# AdelinoR2.net
KiCad netlist of a schematic drawn in EAGLE
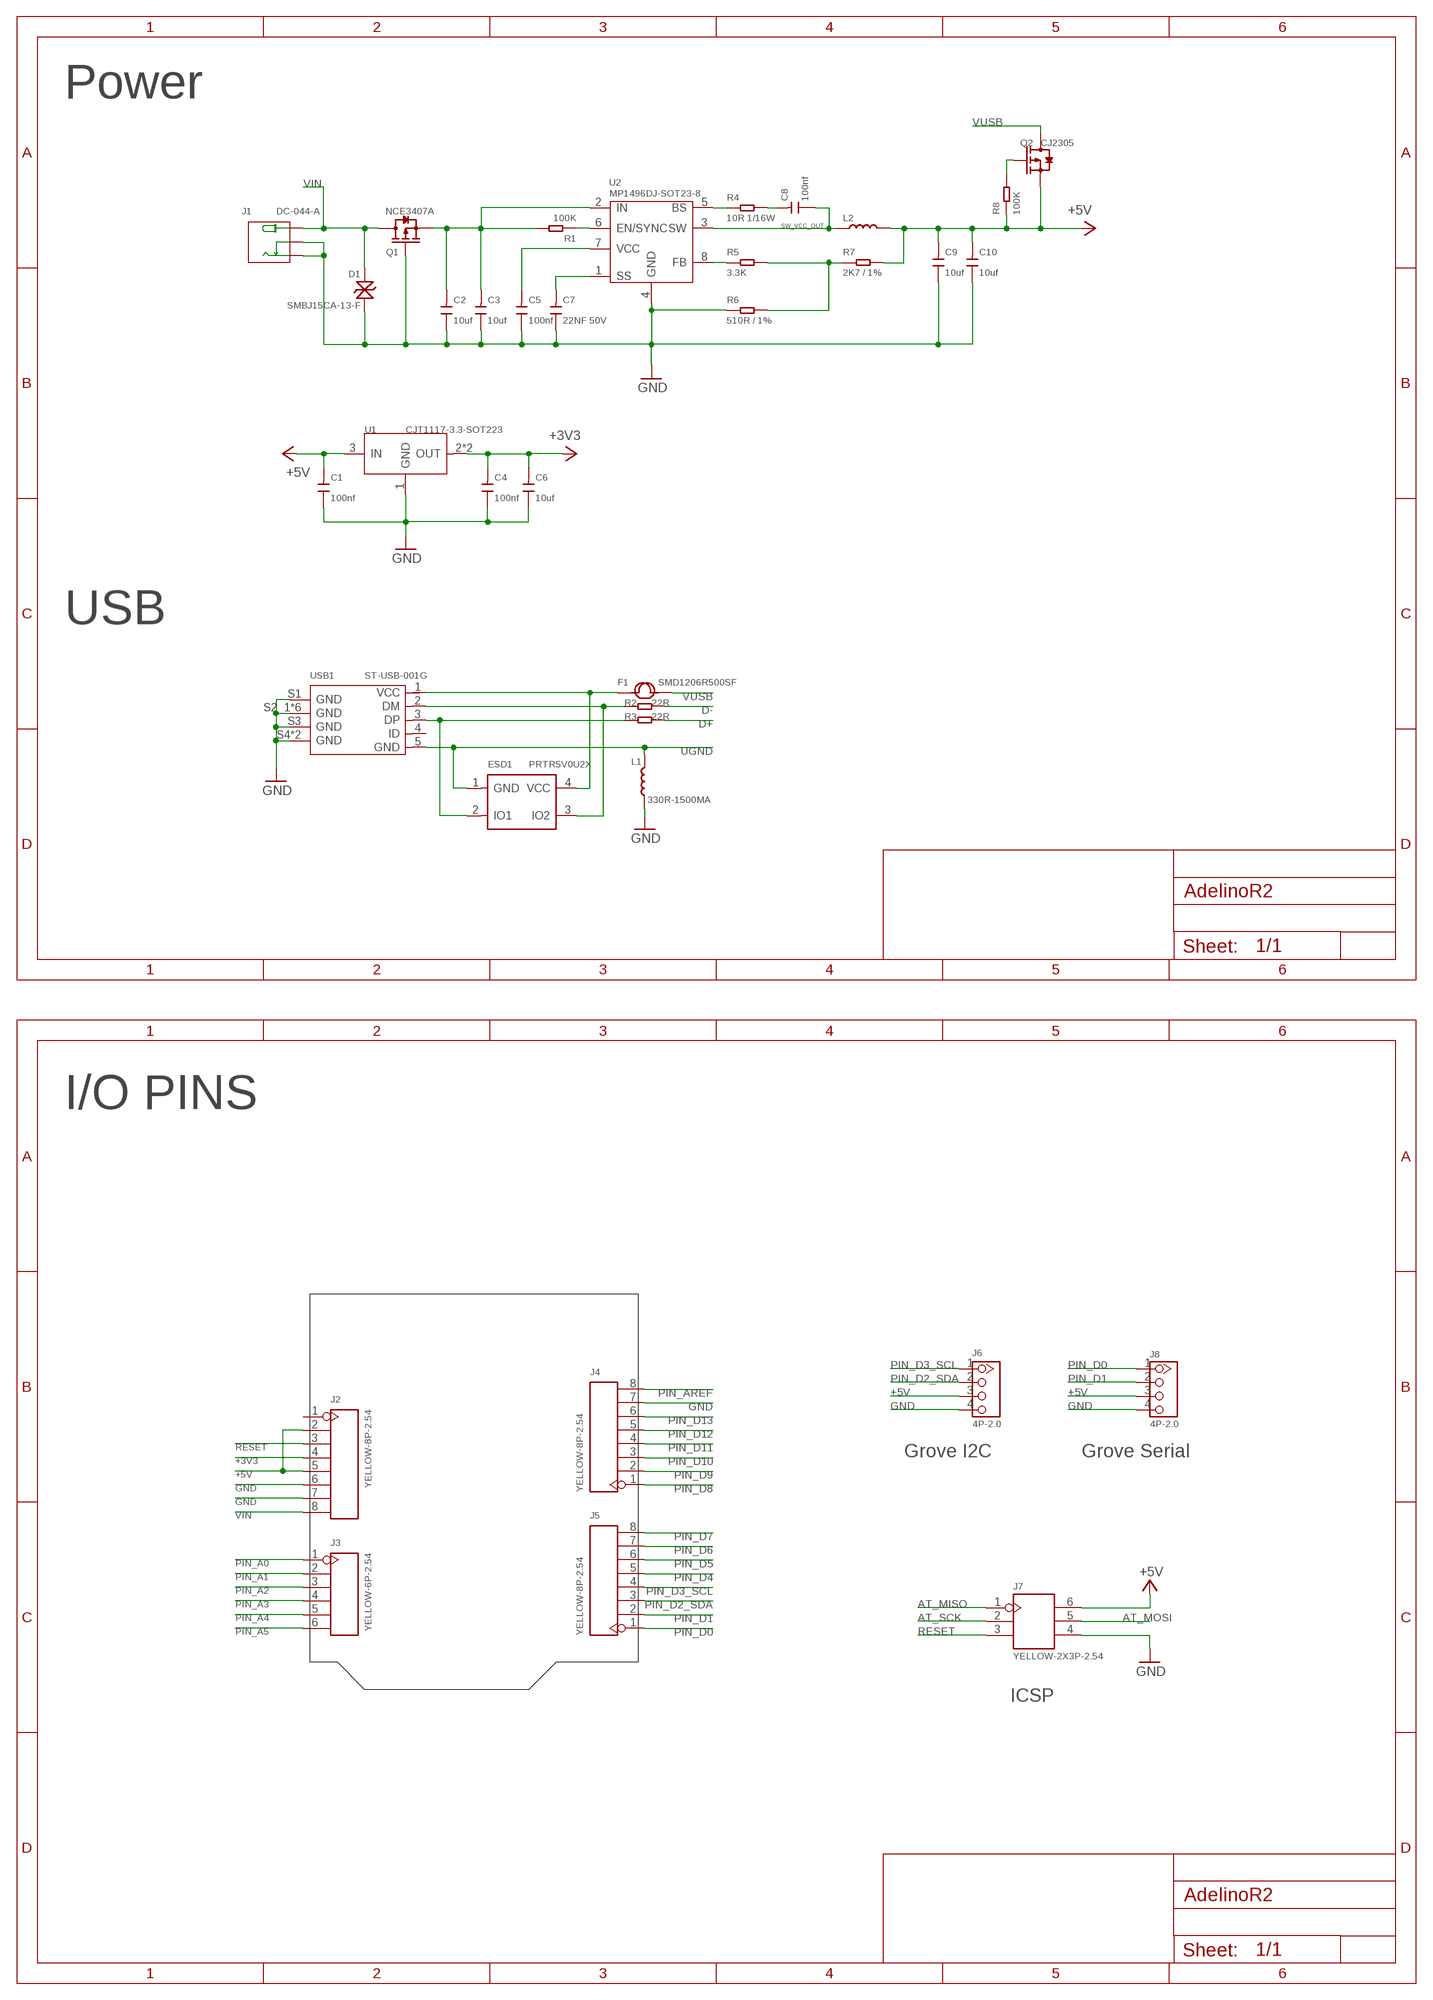
[diagram p0: schematic, sheet 1, part 1 of 2]
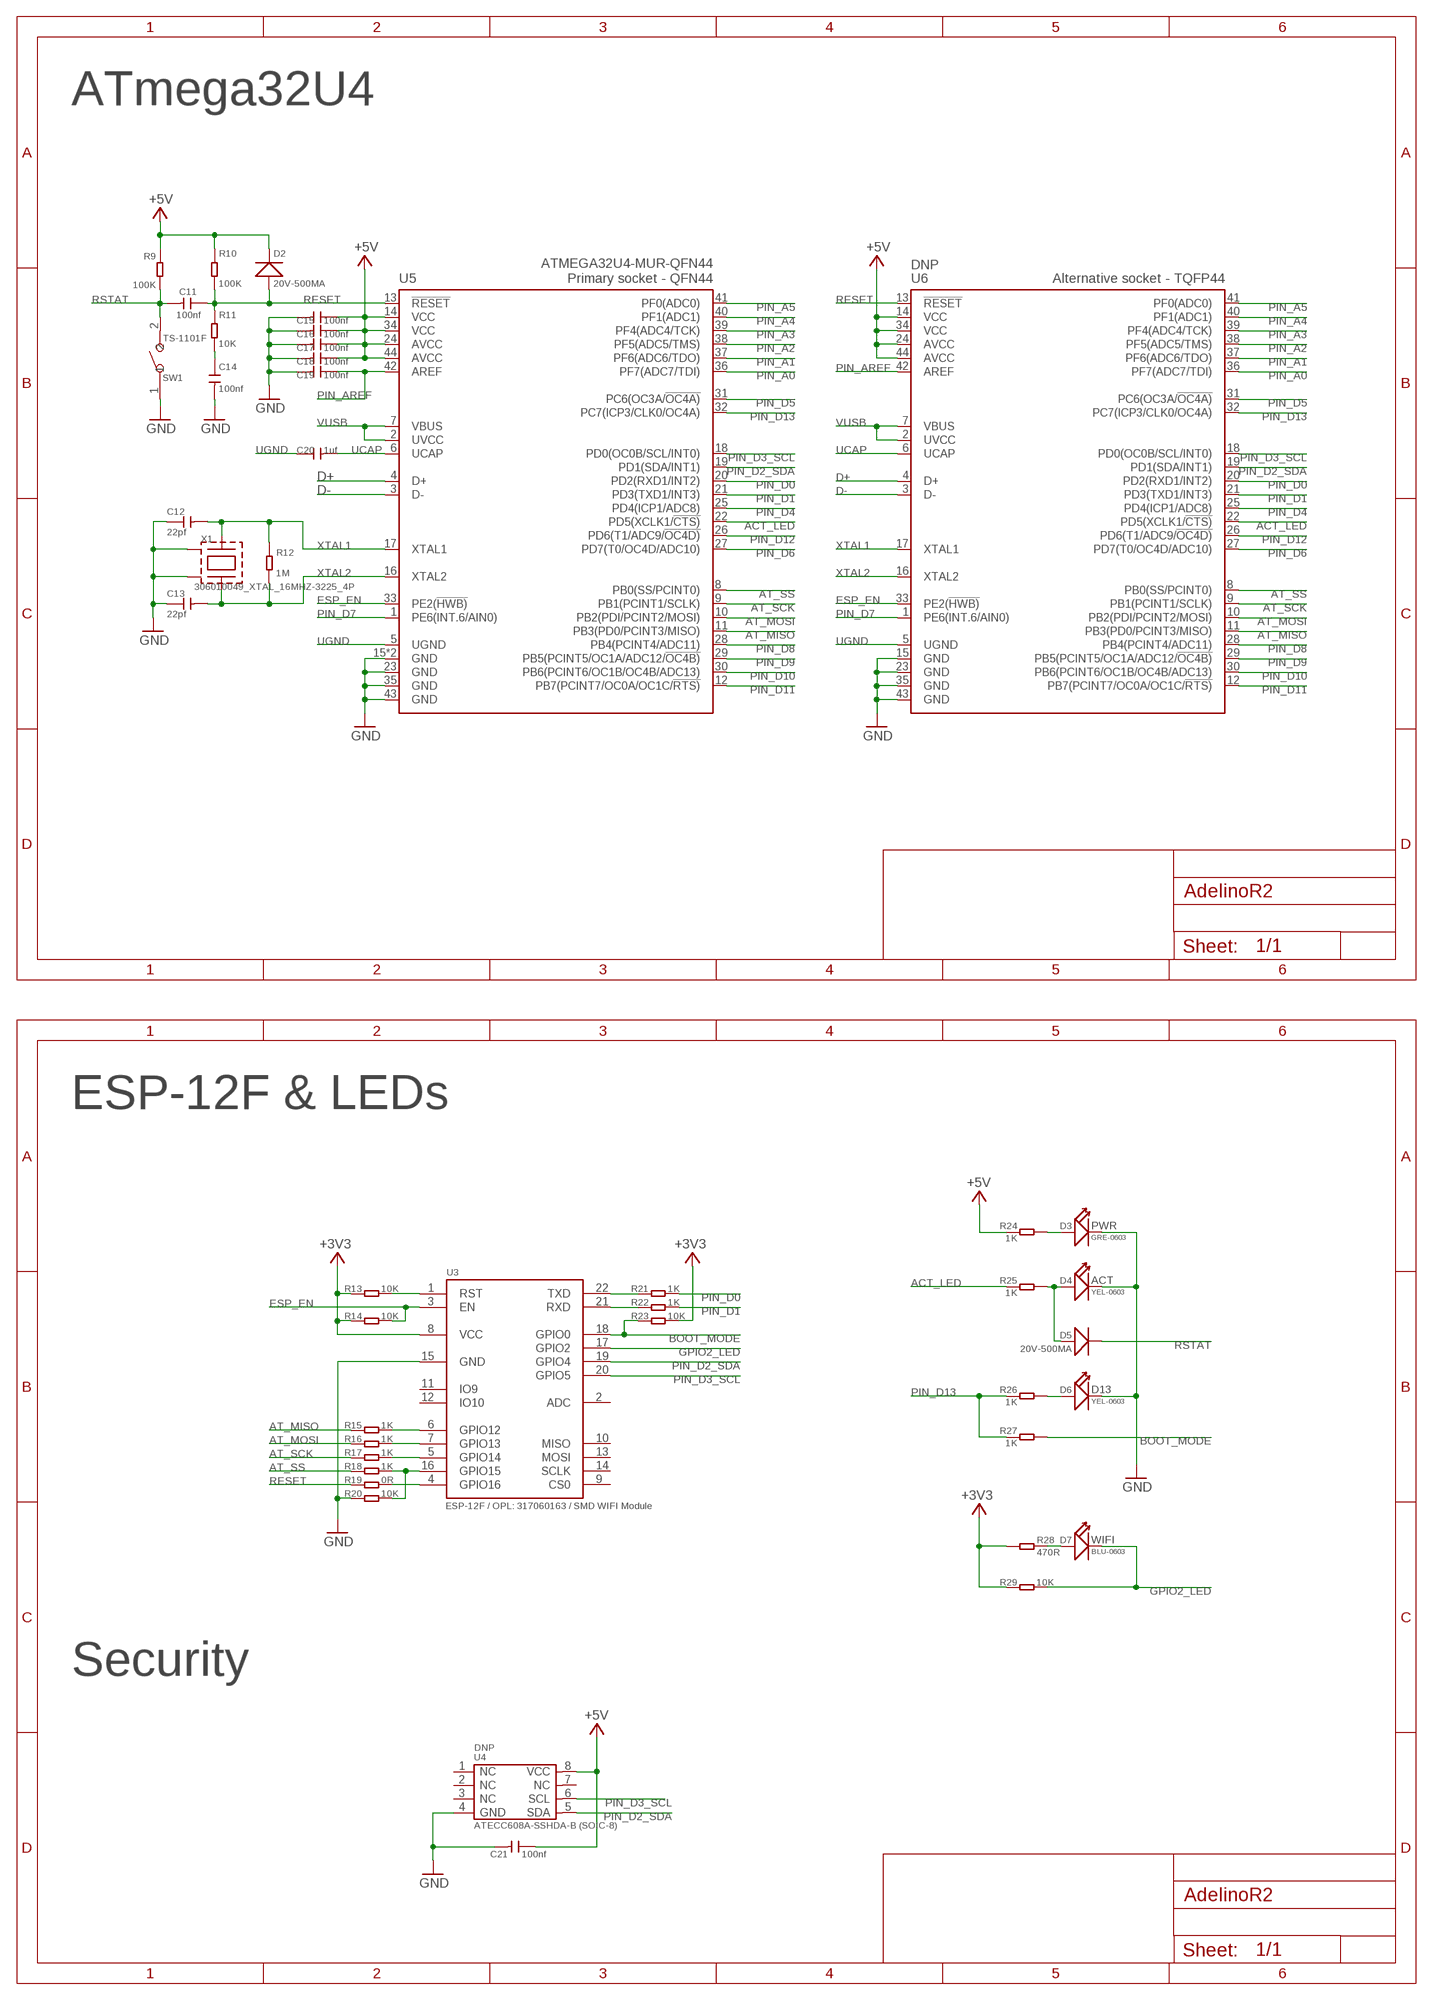
[diagram p1: schematic, sheet 1, part 2 of 2]

(export (version "E")
  (design (tool "Eeschema 10.0.6"))
  (components
    (comp (ref "C1")
      (value "100nf")
      (footprint "eagle-import:C0402")
      (fields (field (name "MPN") "CC0402KRX7R8BB104"))
      (libsource (lib "eagle-import") (part "CERAMIC-100NF-25V-10%-X7R(0402)"))
    )
    (comp (ref "C2")
      (value "10uf")
      (footprint "eagle-import:C0805")
      (fields (field (name "MPN") "CC0805KKX5R8BB106"))
      (libsource (lib "eagle-import") (part "CERAMIC-10UF-25V-10%-X5R(0805)"))
    )
    (comp (ref "C3")
      (value "10uf")
      (footprint "eagle-import:C0805")
      (fields (field (name "MPN") "CC0805KKX5R8BB106"))
      (libsource (lib "eagle-import") (part "CERAMIC-10UF-25V-10%-X5R(0805)"))
    )
    (comp (ref "C4")
      (value "100nf")
      (footprint "eagle-import:C0402")
      (fields (field (name "MPN") "CC0402KRX7R8BB104"))
      (libsource (lib "eagle-import") (part "CERAMIC-100NF-25V-10%-X7R(0402)"))
    )
    (comp (ref "C5")
      (value "100nf")
      (footprint "eagle-import:C0402")
      (fields (field (name "MPN") "CC0402KRX7R8BB104"))
      (libsource (lib "eagle-import") (part "CERAMIC-100NF-25V-10%-X7R(0402)"))
    )
    (comp (ref "C6")
      (value "10uf")
      (footprint "eagle-import:C0805")
      (fields (field (name "MPN") "CC0805KKX5R8BB106"))
      (libsource (lib "eagle-import") (part "CERAMIC-10UF-25V-10%-X5R(0805)"))
    )
    (comp (ref "C7")
      (value "22NF 50V")
      (footprint "eagle-import:C0402")
      (fields (field (name "MPN") "CC0402KRX7R9BB223"))
      (libsource (lib "eagle-import") (part "CERAMIC-22NF-50V-10%-X7R(0402)"))
    )
    (comp (ref "C8")
      (value "100nf")
      (footprint "eagle-import:C0402")
      (fields (field (name "MPN") "CC0402KRX7R8BB104"))
      (libsource (lib "eagle-import") (part "CERAMIC-100NF-25V-10%-X7R(0402)"))
    )
    (comp (ref "C9")
      (value "10uf")
      (footprint "eagle-import:C0805")
      (fields (field (name "MPN") "CC0805KKX5R8BB106"))
      (libsource (lib "eagle-import") (part "CERAMIC-10UF-25V-10%-X5R(0805)"))
    )
    (comp (ref "C10")
      (value "10uf")
      (footprint "eagle-import:C0805")
      (fields (field (name "MPN") "CC0805KKX5R8BB106"))
      (libsource (lib "eagle-import") (part "CERAMIC-10UF-25V-10%-X5R(0805)"))
    )
    (comp (ref "C11")
      (value "100nf")
      (footprint "eagle-import:C0402")
      (fields (field (name "MPN") "CC0402KRX7R8BB104"))
      (libsource (lib "eagle-import") (part "CERAMIC-100NF-25V-10%-X7R(0402)"))
    )
    (comp (ref "C12")
      (value "22pf")
      (footprint "eagle-import:C0402")
      (fields (field (name "MPN") "CC0402JRNPO9BN220"))
      (libsource (lib "eagle-import") (part "CERAMIC-22PF-50V-5%-NPO(0402)"))
    )
    (comp (ref "C13")
      (value "22pf")
      (footprint "eagle-import:C0402")
      (fields (field (name "MPN") "CC0402JRNPO9BN220"))
      (libsource (lib "eagle-import") (part "CERAMIC-22PF-50V-5%-NPO(0402)"))
    )
    (comp (ref "C14")
      (value "100nf")
      (footprint "eagle-import:C0402")
      (fields (field (name "MPN") "CC0402KRX7R8BB104"))
      (libsource (lib "eagle-import") (part "CERAMIC-100NF-25V-10%-X7R(0402)"))
    )
    (comp (ref "C15")
      (value "100nf")
      (footprint "eagle-import:C0402")
      (fields (field (name "MPN") "CC0402KRX7R8BB104"))
      (libsource (lib "eagle-import") (part "CERAMIC-100NF-25V-10%-X7R(0402)"))
    )
    (comp (ref "C16")
      (value "100nf")
      (footprint "eagle-import:C0402")
      (fields (field (name "MPN") "CC0402KRX7R8BB104"))
      (libsource (lib "eagle-import") (part "CERAMIC-100NF-25V-10%-X7R(0402)"))
    )
    (comp (ref "C17")
      (value "100nf")
      (footprint "eagle-import:C0402")
      (fields (field (name "MPN") "CC0402KRX7R8BB104"))
      (libsource (lib "eagle-import") (part "CERAMIC-100NF-25V-10%-X7R(0402)"))
    )
    (comp (ref "C18")
      (value "100nf")
      (footprint "eagle-import:C0402")
      (fields (field (name "MPN") "CC0402KRX7R8BB104"))
      (libsource (lib "eagle-import") (part "CERAMIC-100NF-25V-10%-X7R(0402)"))
    )
    (comp (ref "C19")
      (value "100nf")
      (footprint "eagle-import:C0402")
      (fields (field (name "MPN") "CC0402KRX7R8BB104"))
      (libsource (lib "eagle-import") (part "CERAMIC-100NF-25V-10%-X7R(0402)"))
    )
    (comp (ref "C20")
      (value "1uf")
      (footprint "eagle-import:C0805")
      (fields (field (name "MPN") "CC0805KKX7R8BB105"))
      (libsource (lib "eagle-import") (part "CERAMIC-1UF-25V-10%-X7R(0805)"))
    )
    (comp (ref "C21")
      (value "100nf")
      (footprint "eagle-import:C0402")
      (fields (field (name "MPN") "CC0402KRX7R8BB104"))
      (libsource (lib "eagle-import") (part "CERAMIC-100NF-25V-10%-X7R(0402)"))
    )
    (comp (ref "D1")
      (value "SMBJ15CA-13-F")
      (footprint "eagle-import:DO-214AA")
      (libsource (lib "eagle-import") (part "SMBJ15CA-13-F"))
    )
    (comp (ref "D2")
      (value "20V-500MA")
      (footprint "eagle-import:SOD-123")
      (fields (field (name "MPN") "MBR0520LT1G"))
      (libsource (lib "eagle-import") (part "SMD-DIODE-SCHOTTKY-20V-500MA(SOD-123)P"))
    )
    (comp (ref "D3")
      (value "GRE-0603")
      (footprint "eagle-import:LED-0603")
      (fields (field (name "MPN") "19-217-G7C-AN1P2-3T") (field (name "LABEL") "PWR"))
      (libsource (lib "eagle-import") (part "SMD-LED-CLEAR-GREEN(0603)"))
    )
    (comp (ref "D4")
      (value "YEL-0603")
      (footprint "eagle-import:LED-0603")
      (fields (field (name "MPN") "19-217-Y5C-AM1N1VY-3T") (field (name "LABEL") "ACT"))
      (libsource (lib "eagle-import") (part "SMD-LED-CLEAR-YELLOW(0603)"))
    )
    (comp (ref "D5")
      (value "20V-500MA")
      (footprint "eagle-import:SOD-123")
      (fields (field (name "MPN") "MBR0520LT1G"))
      (libsource (lib "eagle-import") (part "SMD-DIODE-SCHOTTKY-20V-500MA(SOD-123)P"))
    )
    (comp (ref "D6")
      (value "YEL-0603")
      (footprint "eagle-import:LED-0603")
      (fields (field (name "MPN") "19-217-Y5C-AM1N1VY-3T") (field (name "LABEL") "D13"))
      (libsource (lib "eagle-import") (part "SMD-LED-CLEAR-YELLOW(0603)"))
    )
    (comp (ref "D7")
      (value "BLU-0603")
      (footprint "eagle-import:LED-0603")
      (fields (field (name "MPN") "19-217-BHC-ZL1M2RY-3T") (field (name "LABEL") "WIFI"))
      (libsource (lib "eagle-import") (part "SMD-LED-CLEAR-BLUE(0603)"))
    )
    (comp (ref "ESD1")
      (value "PRTR5V0U2X")
      (footprint "eagle-import:SOT-143B")
      (fields (field (name "MPN") "NXP;PRTR5V0U2X,215"))
      (libsource (lib "eagle-import") (part "SMD-DIODE-TVS-5.5V"))
    )
    (comp (ref "F1")
      (value "SMD1206R500SF")
      (footprint "eagle-import:F1206")
      (libsource (lib "eagle-import") (part "SMD-PPTC-500MA(1206)"))
    )
    (comp (ref "J1")
      (value "DC-044-A")
      (footprint "eagle-import:DCJ3P-11.6X9.6X7.0MM")
      (fields (field (name "MPN") "JACK-DC-044-A"))
      (libsource (lib "eagle-import") (part "JACK-DC-044-A"))
    )
    (comp (ref "J2")
      (value "YELLOW-8P-2.54")
      (footprint "eagle-import:H8-2.54")
      (fields (field (name "MPN") "F185-1108A1BSYC1"))
      (libsource (lib "eagle-import") (part "DIP-YELLOW-FEMALE-HEADER(8P-2.54)"))
    )
    (comp (ref "J3")
      (value "YELLOW-6P-2.54")
      (footprint "eagle-import:H6-2.54")
      (fields (field (name "MPN") "F185-1106A1BSYA3"))
      (libsource (lib "eagle-import") (part "DIP-YELLOW-FEMALE-HEADER-VERT(6P-2.54)"))
    )
    (comp (ref "J4")
      (value "YELLOW-8P-2.54")
      (footprint "eagle-import:H8-2.54")
      (fields (field (name "MPN") "F185-1108A1BSYC1"))
      (libsource (lib "eagle-import") (part "DIP-YELLOW-FEMALE-HEADER(8P-2.54)"))
    )
    (comp (ref "J5")
      (value "YELLOW-8P-2.54")
      (footprint "eagle-import:H8-2.54")
      (fields (field (name "MPN") "F185-1108A1BSYC1"))
      (libsource (lib "eagle-import") (part "DIP-YELLOW-FEMALE-HEADER(8P-2.54)"))
    )
    (comp (ref "J6")
      (value "4P-2.0")
      (footprint "eagle-import:HW4-2.0")
      (libsource (lib "eagle-import") (part "GROVE-CONNECTOR-DIP(4P-2.0)"))
    )
    (comp (ref "J7")
      (value "YELLOW-2X3P-2.54")
      (footprint "eagle-import:H2X3-2.54")
      (fields (field (name "MPN") "P125-1203A0BS116A2"))
      (libsource (lib "eagle-import") (part "DIP-YELLOW-MALE-HEADER-VERT(2X3P-2.54)"))
    )
    (comp (ref "J8")
      (value "4P-2.0")
      (footprint "eagle-import:HW4-2.0")
      (libsource (lib "eagle-import") (part "GROVE-CONNECTOR-DIP(4P-2.0)"))
    )
    (comp (ref "L1")
      (value "330R-1500MA")
      (footprint "eagle-import:L0805")
      (fields (field (name "MPN") "BLM21PG331SN1D"))
      (libsource (lib "eagle-import") (part "SMD-FERRITE-BEAD-330R-1500MA(0805)'0805'"))
    )
    (comp (ref "L2")
      (value "10UH-225MA")
      (footprint "eagle-import:L5040S")
      (libsource (lib "eagle-import") (part "SMD-INDUCTOR-10UH-20%-2.35A(2P-5X5X4MM)"))
    )
    (comp (ref "Q1")
      (value "NCE3407A")
      (footprint "eagle-import:SOT-23")
      (libsource (lib "eagle-import") (part "SMD-MOSFET-P-CH-VDC=30V-ID=4.3A-NCE3407A(SOT-23)"))
    )
    (comp (ref "Q2")
      (value "CJ2305")
      (footprint "eagle-import:SOT-23")
      (libsource (lib "eagle-import") (part "SMD-MOSFET-P-CH-8V-4.1A-CJ2305(SOT-23)"))
    )
    (comp (ref "R1")
      (value "100K")
      (footprint "eagle-import:R0402")
      (fields (field (name "MPN") "RC0402FR-07100KL"))
      (libsource (lib "eagle-import") (part "SMD-RES-100K-1%-1/16W(0402)"))
    )
    (comp (ref "R2")
      (value "22R")
      (footprint "eagle-import:R0402")
      (fields (field (name "MPN") "RC0402FR-0722RL"))
      (libsource (lib "eagle-import") (part "SMD-RES-22R-1%-1/16W(0402)"))
    )
    (comp (ref "R3")
      (value "22R")
      (footprint "eagle-import:R0402")
      (fields (field (name "MPN") "RC0402FR-0722RL"))
      (libsource (lib "eagle-import") (part "SMD-RES-22R-1%-1/16W(0402)"))
    )
    (comp (ref "R4")
      (value "10R 1/16W")
      (footprint "eagle-import:R0402")
      (fields (field (name "MPN") "RC0402FR-0710RL"))
      (libsource (lib "eagle-import") (part "SMD-RES-10R-1%-1/16W(0402)"))
    )
    (comp (ref "R5")
      (value "3.3K")
      (footprint "eagle-import:R0402")
      (fields (field (name "MPN") "RC0402JR-073K3L"))
      (libsource (lib "eagle-import") (part "SMD-RES-3.3K-5%-1/16W(0402)"))
    )
    (comp (ref "R6")
      (value "3K / 1%")
      (footprint "eagle-import:R0603")
      (fields (field (name "R") "510R / 1%"))
      (libsource (lib "eagle-import") (part "SMD-RES-510R-1%-1/10W(0603)"))
    )
    (comp (ref "R7")
      (value "2K7 / 1%")
      (footprint "eagle-import:R0603")
      (fields (field (name "R") "2K7 / 1%"))
      (libsource (lib "eagle-import") (part "SMD-RES-2.7K-1%-1/10W(0603)"))
    )
    (comp (ref "R8")
      (value "100K")
      (footprint "eagle-import:R0402")
      (fields (field (name "MPN") "RC0402FR-07100KL"))
      (libsource (lib "eagle-import") (part "SMD-RES-100K-1%-1/16W(0402)"))
    )
    (comp (ref "R9")
      (value "100K")
      (footprint "eagle-import:R0402")
      (fields (field (name "MPN") "RC0402FR-07100KL"))
      (libsource (lib "eagle-import") (part "SMD-RES-100K-1%-1/16W(0402)"))
    )
    (comp (ref "R10")
      (value "100K")
      (footprint "eagle-import:R0402")
      (fields (field (name "MPN") "RC0402FR-07100KL"))
      (libsource (lib "eagle-import") (part "SMD-RES-100K-1%-1/16W(0402)"))
    )
    (comp (ref "R11")
      (value "10K")
      (footprint "eagle-import:R0402")
      (fields (field (name "MPN") "RC0402FR-0710KL"))
      (libsource (lib "eagle-import") (part "SMD-RES-10K-1%-1/16W(0402)"))
    )
    (comp (ref "R12")
      (value "1M")
      (footprint "eagle-import:R0402")
      (fields (field (name "MPN") "RC0402FR-071ML"))
      (libsource (lib "eagle-import") (part "SMD-RES-1M-1%-1/16W(0402)"))
    )
    (comp (ref "R13")
      (value "10K")
      (footprint "eagle-import:R0402")
      (fields (field (name "MPN") "RC0402FR-0710KL"))
      (libsource (lib "eagle-import") (part "SMD-RES-10K-1%-1/16W(0402)"))
    )
    (comp (ref "R14")
      (value "10K")
      (footprint "eagle-import:R0402")
      (fields (field (name "MPN") "RC0402FR-0710KL"))
      (libsource (lib "eagle-import") (part "SMD-RES-10K-1%-1/16W(0402)"))
    )
    (comp (ref "R15")
      (value "1K")
      (footprint "eagle-import:R0402")
      (fields (field (name "MPN") "RC0402JR-071KL"))
      (libsource (lib "eagle-import") (part "SMD-RES-1K-5%-1/16W(0402)"))
    )
    (comp (ref "R16")
      (value "1K")
      (footprint "eagle-import:R0402")
      (fields (field (name "MPN") "RC0402JR-071KL"))
      (libsource (lib "eagle-import") (part "SMD-RES-1K-5%-1/16W(0402)"))
    )
    (comp (ref "R17")
      (value "1K")
      (footprint "eagle-import:R0402")
      (fields (field (name "MPN") "RC0402JR-071KL"))
      (libsource (lib "eagle-import") (part "SMD-RES-1K-5%-1/16W(0402)"))
    )
    (comp (ref "R18")
      (value "1K")
      (footprint "eagle-import:R0402")
      (fields (field (name "MPN") "RC0402JR-071KL"))
      (libsource (lib "eagle-import") (part "SMD-RES-1K-5%-1/16W(0402)"))
    )
    (comp (ref "R19")
      (value "0R")
      (footprint "eagle-import:R0402")
      (fields (field (name "MPN") "RC0402JR-070RL"))
      (libsource (lib "eagle-import") (part "SMD-RES-0R-5%-1/16W(0402)"))
    )
    (comp (ref "R20")
      (value "10K")
      (footprint "eagle-import:R0402")
      (fields (field (name "MPN") "RC0402FR-0710KL"))
      (libsource (lib "eagle-import") (part "SMD-RES-10K-1%-1/16W(0402)"))
    )
    (comp (ref "R21")
      (value "1K")
      (footprint "eagle-import:R0402")
      (fields (field (name "MPN") "RC0402JR-071KL"))
      (libsource (lib "eagle-import") (part "SMD-RES-1K-5%-1/16W(0402)"))
    )
    (comp (ref "R22")
      (value "1K")
      (footprint "eagle-import:R0402")
      (fields (field (name "MPN") "RC0402JR-071KL"))
      (libsource (lib "eagle-import") (part "SMD-RES-1K-5%-1/16W(0402)"))
    )
    (comp (ref "R23")
      (value "10K")
      (footprint "eagle-import:R0402")
      (fields (field (name "MPN") "RC0402FR-0710KL"))
      (libsource (lib "eagle-import") (part "SMD-RES-10K-1%-1/16W(0402)"))
    )
    (comp (ref "R24")
      (value "1K")
      (footprint "eagle-import:R0402")
      (fields (field (name "MPN") "RC0402JR-071KL"))
      (libsource (lib "eagle-import") (part "SMD-RES-1K-5%-1/16W(0402)"))
    )
    (comp (ref "R25")
      (value "1K")
      (footprint "eagle-import:R0402")
      (fields (field (name "MPN") "RC0402JR-071KL"))
      (libsource (lib "eagle-import") (part "SMD-RES-1K-5%-1/16W(0402)"))
    )
    (comp (ref "R26")
      (value "1K")
      (footprint "eagle-import:R0402")
      (fields (field (name "MPN") "RC0402JR-071KL"))
      (libsource (lib "eagle-import") (part "SMD-RES-1K-5%-1/16W(0402)"))
    )
    (comp (ref "R27")
      (value "1K")
      (footprint "eagle-import:R0402")
      (fields (field (name "MPN") "RC0402JR-071KL"))
      (libsource (lib "eagle-import") (part "SMD-RES-1K-5%-1/16W(0402)"))
    )
    (comp (ref "R28")
      (value "470R")
      (footprint "eagle-import:R0402")
      (fields (field (name "MPN") "RC0402JR-07470RL"))
      (libsource (lib "eagle-import") (part "SMD-RES-470R-5%-1/16W(0402)"))
    )
    (comp (ref "R29")
      (value "10K")
      (footprint "eagle-import:R0402")
      (fields (field (name "MPN") "RC0402FR-0710KL"))
      (libsource (lib "eagle-import") (part "SMD-RES-10K-1%-1/16W(0402)"))
    )
    (comp (ref "SW1")
      (value "TS-1101F")
      (footprint "eagle-import:SW2-5.0-6.0X3.0X4.3MM")
      (libsource (lib "eagle-import") (part "DIP-BUTTON(2P-6.0X3.0X4.3MM)-TS-1101F"))
    )
    (comp (ref "U1")
      (value "CJT1117-3.3-SOT223")
      (footprint "eagle-import:SOT-223")
      (fields (field (name "MPN") "CJT1117-3.3"))
      (libsource (lib "eagle-import") (part "PMIC-CJT1117-3.3(SOT223)"))
    )
    (comp (ref "U2")
      (value "MP1496DJ-SOT23-8")
      (footprint "eagle-import:SOT-23-8")
      (fields (field (name "MPN") "MP1496DJ"))
      (libsource (lib "eagle-import") (part "PMIC-MP1496DJ(SOT23-8)"))
    )
    (comp (ref "U3")
      (value "ESP-12F / OPL: 317060163 / SMD WIFI Module")
      (footprint "eagle-import:ESP-12F")
      (libsource (lib "eagle-import") (part "ESP-12F"))
    )
    (comp (ref "U4")
      (value "DNP")
      (footprint "eagle-import:SOIC8-1.27-5X4MM")
      (fields
        (field (name "MPN") "ATECC608")
        (field (name "DESC") "ATECC608A-SSHDA-B (SOIC-8)")
        (field (name "MPN_1") "ATECC608A-SSHDA-B")
      )
      (libsource (lib "eagle-import") (part "ATECC608(SOIC8)"))
    )
    (comp (ref "U5")
      (value "ATMEGA32U4-MUR-QFN44")
      (footprint "eagle-import:QFN44G-0.5-7X7MM")
      (fields (field (name "MPN") "ATMEGA32U4-MUR") (field (name "DESC") "Primary socket - QFN44"))
      (libsource (lib "eagle-import") (part "MCU-ATMEGA32U4-MUR(VQFN44)"))
    )
    (comp (ref "U6")
      (value "DNP")
      (footprint "eagle-import:TQFP44-0.8-9.6X9.6MM")
      (fields (field (name "MPN") "ATMEGA32U4") (field (name "DESC") "Alternative socket - TQFP44"))
      (libsource (lib "eagle-import") (part "MCU-ATMEGA32U4-AU(TQFP44)"))
    )
    (comp (ref "USB1")
      (value "ST-USB-001G")
      (footprint "eagle-import:MICRO-USB5+4P-SMD-0.65-B")
      (libsource (lib "eagle-import") (part "MICRO-USB-SMD-B-WITHOUT-POST-W/P(ST-USB-001G)"))
    )
    (comp (ref "X1")
      (value "306010049_XTAL_16MHZ-3225_4P")
      (footprint "eagle-import:X3225_4P")
      (libsource (lib "eagle-import") (part "306010049_XTAL_16MHZ-3225_4P"))
    )
  )
  (nets
    (net (code "1") (name "+3V3") (class "Default")
      (node (ref "C4") (pin "2") (pinfunction "2_2") (pintype "passive"))
      (node (ref "C6") (pin "2") (pinfunction "2_2") (pintype "passive"))
      (node (ref "J2") (pin "4") (pinfunction "4_4") (pintype "bidirectional"))
      (node (ref "R13") (pin "1") (pinfunction "1_1") (pintype "passive"))
      (node (ref "R14") (pin "1") (pinfunction "1_1") (pintype "passive"))
      (node (ref "R23") (pin "2") (pinfunction "2_2") (pintype "passive"))
      (node (ref "R28") (pin "1") (pinfunction "1_1") (pintype "passive"))
      (node (ref "R29") (pin "1") (pinfunction "1_1") (pintype "passive"))
      (node (ref "U1") (pin "2") (pinfunction "OUT_2") (pintype "bidirectional"))
      (node (ref "U1") (pin "TER") (pinfunction "OUT_TER") (pintype "bidirectional"))
      (node (ref "U3") (pin "8") (pinfunction "VCC_8") (pintype "bidirectional"))
    )
    (net (code "2") (name "+5V") (class "Default")
      (node (ref "C1") (pin "2") (pinfunction "2_2") (pintype "passive"))
      (node (ref "C10") (pin "2") (pinfunction "2_2") (pintype "passive"))
      (node (ref "C15") (pin "1") (pinfunction "1_1") (pintype "passive"))
      (node (ref "C16") (pin "1") (pinfunction "1_1") (pintype "passive"))
      (node (ref "C17") (pin "1") (pinfunction "1_1") (pintype "passive"))
      (node (ref "C18") (pin "1") (pinfunction "1_1") (pintype "passive"))
      (node (ref "C21") (pin "1") (pinfunction "1_1") (pintype "passive"))
      (node (ref "C9") (pin "2") (pinfunction "2_2") (pintype "passive"))
      (node (ref "D2") (pin "-") (pinfunction "-_-") (pintype "passive"))
      (node (ref "J2") (pin "2") (pinfunction "2_2") (pintype "bidirectional"))
      (node (ref "J2") (pin "5") (pinfunction "5_5") (pintype "bidirectional"))
      (node (ref "J6") (pin "3") (pinfunction "3_3") (pintype "bidirectional"))
      (node (ref "J7") (pin "6") (pinfunction "6_6") (pintype "bidirectional"))
      (node (ref "J8") (pin "3") (pinfunction "3_3") (pintype "bidirectional"))
      (node (ref "L2") (pin "2") (pinfunction "2_2") (pintype "passive"))
      (node (ref "Q2") (pin "2") (pinfunction "S_2") (pintype "passive"))
      (node (ref "R10") (pin "2") (pinfunction "2_2") (pintype "passive"))
      (node (ref "R24") (pin "1") (pinfunction "1_1") (pintype "passive"))
      (node (ref "R7") (pin "2") (pinfunction "2_2") (pintype "passive"))
      (node (ref "R8") (pin "1") (pinfunction "1_1") (pintype "passive"))
      (node (ref "R9") (pin "1") (pinfunction "1_1") (pintype "passive"))
      (node (ref "U1") (pin "3") (pinfunction "IN_3") (pintype "bidirectional"))
      (node (ref "U4") (pin "8") (pinfunction "VCC_8") (pintype "power_in"))
      (node (ref "U5") (pin "14") (pinfunction "VCC_14") (pintype "bidirectional"))
      (node (ref "U5") (pin "24") (pinfunction "AVCC_24") (pintype "bidirectional"))
      (node (ref "U5") (pin "34") (pinfunction "VCC_34") (pintype "bidirectional"))
      (node (ref "U5") (pin "44") (pinfunction "AVCC_44") (pintype "bidirectional"))
      (node (ref "U6") (pin "14") (pinfunction "VCC_14") (pintype "bidirectional"))
      (node (ref "U6") (pin "24") (pinfunction "AVCC_24") (pintype "bidirectional"))
      (node (ref "U6") (pin "34") (pinfunction "VCC_34") (pintype "bidirectional"))
      (node (ref "U6") (pin "44") (pinfunction "AVCC_44") (pintype "bidirectional"))
    )
    (net (code "3") (name "/ACT_LED") (class "Default")
      (node (ref "R25") (pin "1") (pinfunction "1_1") (pintype "passive"))
      (node (ref "U5") (pin "22") (pinfunction "PD5(XCLK1/~{CTS})_22") (pintype "bidirectional"))
      (node (ref "U6") (pin "22") (pinfunction "PD5(XCLK1/~{CTS})_22") (pintype "bidirectional"))
    )
    (net (code "4") (name "/AT_MISO") (class "Default")
      (node (ref "J7") (pin "1") (pinfunction "1_1") (pintype "bidirectional"))
      (node (ref "R15") (pin "1") (pinfunction "1_1") (pintype "passive"))
      (node (ref "U5") (pin "11") (pinfunction "PB3(PD0/PCINT3/MISO)_11") (pintype "bidirectional"))
      (node (ref "U6") (pin "11") (pinfunction "PB3(PD0/PCINT3/MISO)_11") (pintype "bidirectional"))
    )
    (net (code "5") (name "/AT_MOSI") (class "Default")
      (node (ref "J7") (pin "5") (pinfunction "5_5") (pintype "bidirectional"))
      (node (ref "R16") (pin "1") (pinfunction "1_1") (pintype "passive"))
      (node (ref "U5") (pin "10") (pinfunction "PB2(PDI/PCINT2/MOSI)_10") (pintype "bidirectional"))
      (node (ref "U6") (pin "10") (pinfunction "PB2(PDI/PCINT2/MOSI)_10") (pintype "bidirectional"))
    )
    (net (code "6") (name "/AT_SCK") (class "Default")
      (node (ref "J7") (pin "2") (pinfunction "2_2") (pintype "bidirectional"))
      (node (ref "R17") (pin "1") (pinfunction "1_1") (pintype "passive"))
      (node (ref "U5") (pin "9") (pinfunction "PB1(PCINT1/SCLK)_9") (pintype "bidirectional"))
      (node (ref "U6") (pin "9") (pinfunction "PB1(PCINT1/SCLK)_9") (pintype "bidirectional"))
    )
    (net (code "7") (name "/AT_SS") (class "Default")
      (node (ref "R18") (pin "1") (pinfunction "1_1") (pintype "passive"))
      (node (ref "U5") (pin "8") (pinfunction "PB0(SS/PCINT0)_8") (pintype "bidirectional"))
      (node (ref "U6") (pin "8") (pinfunction "PB0(SS/PCINT0)_8") (pintype "bidirectional"))
    )
    (net (code "8") (name "/BOOT_MODE") (class "Default")
      (node (ref "R23") (pin "1") (pinfunction "1_1") (pintype "passive"))
      (node (ref "R27") (pin "2") (pinfunction "2_2") (pintype "passive"))
      (node (ref "U3") (pin "18") (pinfunction "GPIO0_18") (pintype "bidirectional"))
    )
    (net (code "9") (name "/D+") (class "Default")
      (node (ref "R3") (pin "2") (pinfunction "2_2") (pintype "passive"))
      (node (ref "U5") (pin "4") (pinfunction "D+_4") (pintype "bidirectional"))
      (node (ref "U6") (pin "4") (pinfunction "D+_4") (pintype "bidirectional"))
    )
    (net (code "10") (name "/D-") (class "Default")
      (node (ref "R2") (pin "2") (pinfunction "2_2") (pintype "passive"))
      (node (ref "U5") (pin "3") (pinfunction "D-_3") (pintype "bidirectional"))
      (node (ref "U6") (pin "3") (pinfunction "D-_3") (pintype "bidirectional"))
    )
    (net (code "11") (name "/ESP_EN") (class "Default")
      (node (ref "R14") (pin "2") (pinfunction "2_2") (pintype "passive"))
      (node (ref "U3") (pin "3") (pinfunction "EN_3") (pintype "bidirectional"))
      (node (ref "U5") (pin "33") (pinfunction "PE2(~{HWB})_33") (pintype "bidirectional"))
      (node (ref "U6") (pin "33") (pinfunction "PE2(~{HWB})_33") (pintype "bidirectional"))
    )
    (net (code "12") (name "/GPIO2_LED") (class "Default")
      (node (ref "D7") (pin "-") (pinfunction "-_-") (pintype "passive"))
      (node (ref "R29") (pin "2") (pinfunction "2_2") (pintype "passive"))
      (node (ref "U3") (pin "17") (pinfunction "GPIO2_17") (pintype "bidirectional"))
    )
    (net (code "13") (name "/PIN_A0") (class "Default")
      (node (ref "J3") (pin "1") (pinfunction "1_1") (pintype "bidirectional"))
      (node (ref "U5") (pin "36") (pinfunction "PF7(ADC7/TDI)_36") (pintype "bidirectional"))
      (node (ref "U6") (pin "36") (pinfunction "PF7(ADC7/TDI)_36") (pintype "bidirectional"))
    )
    (net (code "14") (name "/PIN_A1") (class "Default")
      (node (ref "J3") (pin "2") (pinfunction "2_2") (pintype "bidirectional"))
      (node (ref "U5") (pin "37") (pinfunction "PF6(ADC6/TDO)_37") (pintype "bidirectional"))
      (node (ref "U6") (pin "37") (pinfunction "PF6(ADC6/TDO)_37") (pintype "bidirectional"))
    )
    (net (code "15") (name "/PIN_A2") (class "Default")
      (node (ref "J3") (pin "3") (pinfunction "3_3") (pintype "bidirectional"))
      (node (ref "U5") (pin "38") (pinfunction "PF5(ADC5/TMS)_38") (pintype "bidirectional"))
      (node (ref "U6") (pin "38") (pinfunction "PF5(ADC5/TMS)_38") (pintype "bidirectional"))
    )
    (net (code "16") (name "/PIN_A3") (class "Default")
      (node (ref "J3") (pin "4") (pinfunction "4_4") (pintype "bidirectional"))
      (node (ref "U5") (pin "39") (pinfunction "PF4(ADC4/TCK)_39") (pintype "bidirectional"))
      (node (ref "U6") (pin "39") (pinfunction "PF4(ADC4/TCK)_39") (pintype "bidirectional"))
    )
    (net (code "17") (name "/PIN_A4") (class "Default")
      (node (ref "J3") (pin "5") (pinfunction "5_5") (pintype "bidirectional"))
      (node (ref "U5") (pin "40") (pinfunction "PF1(ADC1)_40") (pintype "bidirectional"))
      (node (ref "U6") (pin "40") (pinfunction "PF1(ADC1)_40") (pintype "bidirectional"))
    )
    (net (code "18") (name "/PIN_A5") (class "Default")
      (node (ref "J3") (pin "6") (pinfunction "6_6") (pintype "bidirectional"))
      (node (ref "U5") (pin "41") (pinfunction "PF0(ADC0)_41") (pintype "bidirectional"))
      (node (ref "U6") (pin "41") (pinfunction "PF0(ADC0)_41") (pintype "bidirectional"))
    )
    (net (code "19") (name "/PIN_AREF") (class "Default")
      (node (ref "C19") (pin "1") (pinfunction "1_1") (pintype "passive"))
      (node (ref "J4") (pin "8") (pinfunction "8_8") (pintype "bidirectional"))
      (node (ref "U5") (pin "42") (pinfunction "AREF_42") (pintype "bidirectional"))
      (node (ref "U6") (pin "42") (pinfunction "AREF_42") (pintype "bidirectional"))
    )
    (net (code "20") (name "/PIN_D0") (class "Default")
      (node (ref "J5") (pin "1") (pinfunction "1_1") (pintype "bidirectional"))
      (node (ref "J8") (pin "1") (pinfunction "1_1") (pintype "bidirectional"))
      (node (ref "R21") (pin "2") (pinfunction "2_2") (pintype "passive"))
      (node (ref "U5") (pin "20") (pinfunction "PD2(RXD1/INT2)_20") (pintype "bidirectional"))
      (node (ref "U6") (pin "20") (pinfunction "PD2(RXD1/INT2)_20") (pintype "bidirectional"))
    )
    (net (code "21") (name "/PIN_D1") (class "Default")
      (node (ref "J5") (pin "2") (pinfunction "2_2") (pintype "bidirectional"))
      (node (ref "J8") (pin "2") (pinfunction "2_2") (pintype "bidirectional"))
      (node (ref "R22") (pin "2") (pinfunction "2_2") (pintype "passive"))
      (node (ref "U5") (pin "21") (pinfunction "PD3(TXD1/INT3)_21") (pintype "bidirectional"))
      (node (ref "U6") (pin "21") (pinfunction "PD3(TXD1/INT3)_21") (pintype "bidirectional"))
    )
    (net (code "22") (name "/PIN_D2_SDA") (class "Default")
      (node (ref "J5") (pin "3") (pinfunction "3_3") (pintype "bidirectional"))
      (node (ref "J6") (pin "2") (pinfunction "2_2") (pintype "bidirectional"))
      (node (ref "U3") (pin "19") (pinfunction "GPIO4_19") (pintype "bidirectional"))
      (node (ref "U4") (pin "5") (pinfunction "SDA_5") (pintype "bidirectional"))
      (node (ref "U5") (pin "19") (pinfunction "PD1(SDA/INT1)_19") (pintype "bidirectional"))
      (node (ref "U6") (pin "19") (pinfunction "PD1(SDA/INT1)_19") (pintype "bidirectional"))
    )
    (net (code "23") (name "/PIN_D3_SCL") (class "Default")
      (node (ref "J5") (pin "4") (pinfunction "4_4") (pintype "bidirectional"))
      (node (ref "J6") (pin "1") (pinfunction "1_1") (pintype "bidirectional"))
      (node (ref "U3") (pin "20") (pinfunction "GPIO5_20") (pintype "bidirectional"))
      (node (ref "U4") (pin "6") (pinfunction "SCL_6") (pintype "input"))
      (node (ref "U5") (pin "18") (pinfunction "PD0(OC0B/SCL/INT0)_18") (pintype "bidirectional"))
      (node (ref "U6") (pin "18") (pinfunction "PD0(OC0B/SCL/INT0)_18") (pintype "bidirectional"))
    )
    (net (code "24") (name "/PIN_D4") (class "Default")
      (node (ref "J5") (pin "5") (pinfunction "5_5") (pintype "bidirectional"))
      (node (ref "U5") (pin "25") (pinfunction "PD4(ICP1/ADC8)_25") (pintype "bidirectional"))
      (node (ref "U6") (pin "25") (pinfunction "PD4(ICP1/ADC8)_25") (pintype "bidirectional"))
    )
    (net (code "25") (name "/PIN_D5") (class "Default")
      (node (ref "J5") (pin "6") (pinfunction "6_6") (pintype "bidirectional"))
      (node (ref "U5") (pin "31") (pinfunction "PC6(OC3A/~{OC4A})_31") (pintype "bidirectional"))
      (node (ref "U6") (pin "31") (pinfunction "PC6(OC3A/~{OC4A})_31") (pintype "bidirectional"))
    )
    (net (code "26") (name "/PIN_D6") (class "Default")
      (node (ref "J5") (pin "7") (pinfunction "7_7") (pintype "bidirectional"))
      (node (ref "U5") (pin "27") (pinfunction "PD7(T0/OC4D/ADC10)_27") (pintype "bidirectional"))
      (node (ref "U6") (pin "27") (pinfunction "PD7(T0/OC4D/ADC10)_27") (pintype "bidirectional"))
    )
    (net (code "27") (name "/PIN_D7") (class "Default")
      (node (ref "J5") (pin "8") (pinfunction "8_8") (pintype "bidirectional"))
      (node (ref "U5") (pin "1") (pinfunction "PE6(INT.6/AIN0)_1") (pintype "bidirectional"))
      (node (ref "U6") (pin "1") (pinfunction "PE6(INT.6/AIN0)_1") (pintype "bidirectional"))
    )
    (net (code "28") (name "/PIN_D8") (class "Default")
      (node (ref "J4") (pin "1") (pinfunction "1_1") (pintype "bidirectional"))
      (node (ref "U5") (pin "28") (pinfunction "PB4(PCINT4/ADC11)_28") (pintype "bidirectional"))
      (node (ref "U6") (pin "28") (pinfunction "PB4(PCINT4/ADC11)_28") (pintype "bidirectional"))
    )
    (net (code "29") (name "/PIN_D9") (class "Default")
      (node (ref "J4") (pin "2") (pinfunction "2_2") (pintype "bidirectional"))
      (node (ref "U5") (pin "29") (pinfunction "PB5(PCINT5/OC1A/ADC12/~{OC4B})_29") (pintype "bidirectional"))
      (node (ref "U6") (pin "29") (pinfunction "PB5(PCINT5/OC1A/ADC12/~{OC4B})_29") (pintype "bidirectional"))
    )
    (net (code "30") (name "/PIN_D10") (class "Default")
      (node (ref "J4") (pin "3") (pinfunction "3_3") (pintype "bidirectional"))
      (node (ref "U5") (pin "30") (pinfunction "PB6(PCINT6/OC1B/OC4B/ADC13)_30") (pintype "bidirectional"))
      (node (ref "U6") (pin "30") (pinfunction "PB6(PCINT6/OC1B/OC4B/ADC13)_30") (pintype "bidirectional"))
    )
    (net (code "31") (name "/PIN_D11") (class "Default")
      (node (ref "J4") (pin "4") (pinfunction "4_4") (pintype "bidirectional"))
      (node (ref "U5") (pin "12") (pinfunction "PB7(PCINT7/OC0A/OC1C/~{RTS})_12") (pintype "bidirectional"))
      (node (ref "U6") (pin "12") (pinfunction "PB7(PCINT7/OC0A/OC1C/~{RTS})_12") (pintype "bidirectional"))
    )
    (net (code "32") (name "/PIN_D12") (class "Default")
      (node (ref "J4") (pin "5") (pinfunction "5_5") (pintype "bidirectional"))
      (node (ref "U5") (pin "26") (pinfunction "PD6(T1/ADC9/~{OC4D})_26") (pintype "bidirectional"))
      (node (ref "U6") (pin "26") (pinfunction "PD6(T1/ADC9/~{OC4D})_26") (pintype "bidirectional"))
    )
    (net (code "33") (name "/PIN_D13") (class "Default")
      (node (ref "J4") (pin "6") (pinfunction "6_6") (pintype "bidirectional"))
      (node (ref "R26") (pin "1") (pinfunction "1_1") (pintype "passive"))
      (node (ref "R27") (pin "1") (pinfunction "1_1") (pintype "passive"))
      (node (ref "U5") (pin "32") (pinfunction "PC7(ICP3/CLK0/OC4A)_32") (pintype "bidirectional"))
      (node (ref "U6") (pin "32") (pinfunction "PC7(ICP3/CLK0/OC4A)_32") (pintype "bidirectional"))
    )
    (net (code "34") (name "/RESET") (class "Default")
      (node (ref "C11") (pin "1") (pinfunction "1_1") (pintype "passive"))
      (node (ref "D2") (pin "+") (pinfunction "+_+") (pintype "passive"))
      (node (ref "J2") (pin "3") (pinfunction "3_3") (pintype "bidirectional"))
      (node (ref "J7") (pin "3") (pinfunction "3_3") (pintype "bidirectional"))
      (node (ref "R10") (pin "1") (pinfunction "1_1") (pintype "passive"))
      (node (ref "R11") (pin "1") (pinfunction "1_1") (pintype "passive"))
      (node (ref "R19") (pin "1") (pinfunction "1_1") (pintype "passive"))
      (node (ref "U5") (pin "13") (pinfunction "~{RESET}_13") (pintype "bidirectional"))
      (node (ref "U6") (pin "13") (pinfunction "~{RESET}_13") (pintype "bidirectional"))
    )
    (net (code "35") (name "/RSTAT") (class "Default")
      (node (ref "C11") (pin "2") (pinfunction "2_2") (pintype "passive"))
      (node (ref "D5") (pin "-") (pinfunction "-_-") (pintype "passive"))
      (node (ref "R9") (pin "2") (pinfunction "2_2") (pintype "passive"))
      (node (ref "SW1") (pin "2") (pinfunction "2_2") (pintype "bidirectional"))
    )
    (net (code "36") (name "/SW_VCC_OUT") (class "Default")
      (node (ref "C8") (pin "1") (pinfunction "1_1") (pintype "passive"))
      (node (ref "L2") (pin "1") (pinfunction "1_1") (pintype "passive"))
      (node (ref "U2") (pin "3") (pinfunction "SW_3") (pintype "bidirectional"))
    )
    (net (code "37") (name "/UCAP") (class "Default")
      (node (ref "C20") (pin "2") (pinfunction "2_2") (pintype "passive"))
      (node (ref "U5") (pin "6") (pinfunction "UCAP_6") (pintype "bidirectional"))
      (node (ref "U6") (pin "6") (pinfunction "UCAP_6") (pintype "bidirectional"))
    )
    (net (code "38") (name "/UGND") (class "Default")
      (node (ref "C20") (pin "1") (pinfunction "1_1") (pintype "passive"))
      (node (ref "ESD1") (pin "1") (pinfunction "GND_1") (pintype "bidirectional"))
      (node (ref "L1") (pin "2") (pinfunction "2_2") (pintype "passive"))
      (node (ref "U5") (pin "5") (pinfunction "UGND_5") (pintype "bidirectional"))
      (node (ref "U6") (pin "5") (pinfunction "UGND_5") (pintype "bidirectional"))
      (node (ref "USB1") (pin "5") (pinfunction "GND_5") (pintype "bidirectional"))
    )
    (net (code "39") (name "/VIN") (class "Default")
      (node (ref "D1") (pin "-") (pinfunction "-_-") (pintype "passive"))
      (node (ref "J1") (pin "VCC1") (pinfunction "+_VCC1") (pintype "bidirectional"))
      (node (ref "J1") (pin "VCC2") (pinfunction "+_VCC2") (pintype "bidirectional"))
      (node (ref "J1") (pin "VCC3") (pinfunction "+_VCC3") (pintype "bidirectional"))
      (node (ref "J1") (pin "VCC4") (pinfunction "+_VCC4") (pintype "bidirectional"))
      (node (ref "J2") (pin "8") (pinfunction "8_8") (pintype "bidirectional"))
      (node (ref "Q1") (pin "3") (pinfunction "D_3") (pintype "passive"))
    )
    (net (code "40") (name "/VUSB") (class "Default")
      (node (ref "F1") (pin "2") (pinfunction "2_2") (pintype "bidirectional"))
      (node (ref "Q2") (pin "3") (pinfunction "D_3") (pintype "passive"))
      (node (ref "U5") (pin "2") (pinfunction "UVCC_2") (pintype "bidirectional"))
      (node (ref "U5") (pin "7") (pinfunction "VBUS_7") (pintype "bidirectional"))
      (node (ref "U6") (pin "2") (pinfunction "UVCC_2") (pintype "bidirectional"))
      (node (ref "U6") (pin "7") (pinfunction "VBUS_7") (pintype "bidirectional"))
    )
    (net (code "41") (name "/XTAL1") (class "Default")
      (node (ref "C12") (pin "2") (pinfunction "2_2") (pintype "passive"))
      (node (ref "R12") (pin "2") (pinfunction "2_2") (pintype "passive"))
      (node (ref "U5") (pin "17") (pinfunction "XTAL1_17") (pintype "bidirectional"))
      (node (ref "U6") (pin "17") (pinfunction "XTAL1_17") (pintype "bidirectional"))
      (node (ref "X1") (pin "P$1") (pinfunction "P$1_P$1") (pintype "passive"))
    )
    (net (code "42") (name "/XTAL2") (class "Default")
      (node (ref "C13") (pin "2") (pinfunction "2_2") (pintype "passive"))
      (node (ref "R12") (pin "1") (pinfunction "1_1") (pintype "passive"))
      (node (ref "U5") (pin "16") (pinfunction "XTAL2_16") (pintype "bidirectional"))
      (node (ref "U6") (pin "16") (pinfunction "XTAL2_16") (pintype "bidirectional"))
      (node (ref "X1") (pin "P$3") (pinfunction "P$2_P$3") (pintype "passive"))
    )
    (net (code "43") (name "GND") (class "Default")
      (node (ref "C1") (pin "1") (pinfunction "1_1") (pintype "passive"))
      (node (ref "C10") (pin "1") (pinfunction "1_1") (pintype "passive"))
      (node (ref "C12") (pin "1") (pinfunction "1_1") (pintype "passive"))
      (node (ref "C13") (pin "1") (pinfunction "1_1") (pintype "passive"))
      (node (ref "C14") (pin "2") (pinfunction "2_2") (pintype "passive"))
      (node (ref "C15") (pin "2") (pinfunction "2_2") (pintype "passive"))
      (node (ref "C16") (pin "2") (pinfunction "2_2") (pintype "passive"))
      (node (ref "C17") (pin "2") (pinfunction "2_2") (pintype "passive"))
      (node (ref "C18") (pin "2") (pinfunction "2_2") (pintype "passive"))
      (node (ref "C19") (pin "2") (pinfunction "2_2") (pintype "passive"))
      (node (ref "C2") (pin "1") (pinfunction "1_1") (pintype "passive"))
      (node (ref "C21") (pin "2") (pinfunction "2_2") (pintype "passive"))
      (node (ref "C3") (pin "1") (pinfunction "1_1") (pintype "passive"))
      (node (ref "C4") (pin "1") (pinfunction "1_1") (pintype "passive"))
      (node (ref "C5") (pin "1") (pinfunction "1_1") (pintype "passive"))
      (node (ref "C6") (pin "1") (pinfunction "1_1") (pintype "passive"))
      (node (ref "C7") (pin "1") (pinfunction "1_1") (pintype "passive"))
      (node (ref "C9") (pin "1") (pinfunction "1_1") (pintype "passive"))
      (node (ref "D1") (pin "+") (pinfunction "+_+") (pintype "passive"))
      (node (ref "D3") (pin "-") (pinfunction "-_-") (pintype "passive"))
      (node (ref "D4") (pin "-") (pinfunction "-_-") (pintype "passive"))
      (node (ref "D6") (pin "-") (pinfunction "-_-") (pintype "passive"))
      (node (ref "J1") (pin "CDN1") (pinfunction "CDN_CDN1") (pintype "bidirectional"))
      (node (ref "J1") (pin "CDN2") (pinfunction "CDN_CDN2") (pintype "bidirectional"))
      (node (ref "J1") (pin "CDN3") (pinfunction "CDN_CDN3") (pintype "bidirectional"))
      (node (ref "J1") (pin "CDN4") (pinfunction "CDN_CDN4") (pintype "bidirectional"))
      (node (ref "J1") (pin "GND1") (pinfunction "-_GND1") (pintype "bidirectional"))
      (node (ref "J1") (pin "GND2") (pinfunction "-_GND2") (pintype "bidirectional"))
      (node (ref "J1") (pin "GND3") (pinfunction "-_GND3") (pintype "bidirectional"))
      (node (ref "J1") (pin "GND4") (pinfunction "-_GND4") (pintype "bidirectional"))
      (node (ref "J2") (pin "6") (pinfunction "6_6") (pintype "bidirectional"))
      (node (ref "J2") (pin "7") (pinfunction "7_7") (pintype "bidirectional"))
      (node (ref "J4") (pin "7") (pinfunction "7_7") (pintype "bidirectional"))
      (node (ref "J6") (pin "4") (pinfunction "4_4") (pintype "bidirectional"))
      (node (ref "J7") (pin "4") (pinfunction "4_4") (pintype "bidirectional"))
      (node (ref "J8") (pin "4") (pinfunction "4_4") (pintype "bidirectional"))
      (node (ref "L1") (pin "1") (pinfunction "1_1") (pintype "passive"))
      (node (ref "Q1") (pin "1") (pinfunction "G_1") (pintype "passive"))
      (node (ref "R20") (pin "1") (pinfunction "1_1") (pintype "passive"))
      (node (ref "R6") (pin "1") (pinfunction "1_1") (pintype "passive"))
      (node (ref "SW1") (pin "1") (pinfunction "1_1") (pintype "bidirectional"))
      (node (ref "U1") (pin "1") (pinfunction "GND_1") (pintype "bidirectional"))
      (node (ref "U2") (pin "4") (pinfunction "GND_4") (pintype "bidirectional"))
      (node (ref "U3") (pin "15") (pinfunction "GND_15") (pintype "bidirectional"))
      (node (ref "U4") (pin "4") (pinfunction "GND_4") (pintype "power_in"))
      (node (ref "U5") (pin "15") (pinfunction "GND_15") (pintype "bidirectional"))
      (node (ref "U5") (pin "23") (pinfunction "GND_23") (pintype "bidirectional"))
      (node (ref "U5") (pin "35") (pinfunction "GND_35") (pintype "bidirectional"))
      (node (ref "U5") (pin "43") (pinfunction "GND_43") (pintype "bidirectional"))
      (node (ref "U5") (pin "TAB") (pinfunction "GND_TAB") (pintype "bidirectional"))
      (node (ref "U6") (pin "15") (pinfunction "GND_15") (pintype "bidirectional"))
      (node (ref "U6") (pin "23") (pinfunction "GND_23") (pintype "bidirectional"))
      (node (ref "U6") (pin "35") (pinfunction "GND_35") (pintype "bidirectional"))
      (node (ref "U6") (pin "43") (pinfunction "GND_43") (pintype "bidirectional"))
      (node (ref "USB1") (pin "S1") (pinfunction "GND_S1") (pintype "bidirectional"))
      (node (ref "USB1") (pin "S2_1") (pinfunction "GND_S2_1") (pintype "bidirectional"))
      (node (ref "USB1") (pin "S2_2") (pinfunction "GND_S2_2") (pintype "bidirectional"))
      (node (ref "USB1") (pin "S2_3") (pinfunction "GND_S2_3") (pintype "bidirectional"))
      (node (ref "USB1") (pin "S3") (pinfunction "GND_S3") (pintype "bidirectional"))
      (node (ref "USB1") (pin "S4") (pinfunction "GND_S4") (pintype "bidirectional"))
      (node (ref "USB1") (pin "S5_1") (pinfunction "GND_S5_1") (pintype "bidirectional"))
      (node (ref "USB1") (pin "S5_2") (pinfunction "GND_S5_2") (pintype "bidirectional"))
      (node (ref "USB1") (pin "S5_3") (pinfunction "GND_S5_3") (pintype "bidirectional"))
      (node (ref "USB1") (pin "S6") (pinfunction "GND_S6") (pintype "bidirectional"))
      (node (ref "X1") (pin "P$2") (pinfunction "GND1_P$2") (pintype "power_in"))
      (node (ref "X1") (pin "P$4") (pinfunction "GND2_P$4") (pintype "power_in"))
    )
    (net (code "44") (name "Net-(C8-Pad2)") (class "Default")
      (node (ref "C8") (pin "2") (pinfunction "2_2") (pintype "passive"))
      (node (ref "R4") (pin "2") (pinfunction "2_2") (pintype "passive"))
    )
    (net (code "45") (name "Net-(C14-Pad1)") (class "Default")
      (node (ref "C14") (pin "1") (pinfunction "1_1") (pintype "passive"))
      (node (ref "R11") (pin "2") (pinfunction "2_2") (pintype "passive"))
    )
    (net (code "46") (name "Net-(D3-Pad+)") (class "Default")
      (node (ref "D3") (pin "+") (pinfunction "+_+") (pintype "passive"))
      (node (ref "R24") (pin "2") (pinfunction "2_2") (pintype "passive"))
    )
    (net (code "47") (name "Net-(D4-Pad+)") (class "Default")
      (node (ref "D4") (pin "+") (pinfunction "+_+") (pintype "passive"))
      (node (ref "D5") (pin "+") (pinfunction "+_+") (pintype "passive"))
      (node (ref "R25") (pin "2") (pinfunction "2_2") (pintype "passive"))
    )
    (net (code "48") (name "Net-(D6-Pad+)") (class "Default")
      (node (ref "D6") (pin "+") (pinfunction "+_+") (pintype "passive"))
      (node (ref "R26") (pin "2") (pinfunction "2_2") (pintype "passive"))
    )
    (net (code "49") (name "Net-(D7-Pad+)") (class "Default")
      (node (ref "D7") (pin "+") (pinfunction "+_+") (pintype "passive"))
      (node (ref "R28") (pin "2") (pinfunction "2_2") (pintype "passive"))
    )
    (net (code "50") (name "Net-(ESD1-IO1)") (class "Default")
      (node (ref "ESD1") (pin "2") (pinfunction "IO1_2") (pintype "bidirectional"))
      (node (ref "R3") (pin "1") (pinfunction "1_1") (pintype "passive"))
      (node (ref "USB1") (pin "3") (pinfunction "DP_3") (pintype "bidirectional"))
    )
    (net (code "51") (name "Net-(ESD1-IO2)") (class "Default")
      (node (ref "ESD1") (pin "3") (pinfunction "IO2_3") (pintype "bidirectional"))
      (node (ref "R2") (pin "1") (pinfunction "1_1") (pintype "passive"))
      (node (ref "USB1") (pin "2") (pinfunction "DM_2") (pintype "bidirectional"))
    )
    (net (code "52") (name "Net-(ESD1-VCC)") (class "Default")
      (node (ref "ESD1") (pin "4") (pinfunction "VCC_4") (pintype "bidirectional"))
      (node (ref "F1") (pin "1") (pinfunction "1_1") (pintype "bidirectional"))
      (node (ref "USB1") (pin "1") (pinfunction "VCC_1") (pintype "bidirectional"))
    )
    (net (code "53") (name "Net-(Q1-S)") (class "Default")
      (node (ref "C2") (pin "2") (pinfunction "2_2") (pintype "passive"))
      (node (ref "C3") (pin "2") (pinfunction "2_2") (pintype "passive"))
      (node (ref "Q1") (pin "2") (pinfunction "S_2") (pintype "passive"))
      (node (ref "R1") (pin "2") (pinfunction "2_2") (pintype "passive"))
      (node (ref "U2") (pin "2") (pinfunction "IN_2") (pintype "bidirectional"))
    )
    (net (code "54") (name "Net-(Q2-G)") (class "Default")
      (node (ref "Q2") (pin "1") (pinfunction "G_1") (pintype "passive"))
      (node (ref "R8") (pin "2") (pinfunction "2_2") (pintype "passive"))
    )
    (net (code "55") (name "Net-(R5-Pad2)") (class "Default")
      (node (ref "R5") (pin "2") (pinfunction "2_2") (pintype "passive"))
      (node (ref "R6") (pin "2") (pinfunction "2_2") (pintype "passive"))
      (node (ref "R7") (pin "1") (pinfunction "1_1") (pintype "passive"))
    )
    (net (code "56") (name "Net-(U2-BS)") (class "Default")
      (node (ref "R4") (pin "1") (pinfunction "1_1") (pintype "passive"))
      (node (ref "U2") (pin "5") (pinfunction "BS_5") (pintype "bidirectional"))
    )
    (net (code "57") (name "Net-(U2-EN{slash}SYNC)") (class "Default")
      (node (ref "R1") (pin "1") (pinfunction "1_1") (pintype "passive"))
      (node (ref "U2") (pin "6") (pinfunction "EN/SYNC_6") (pintype "bidirectional"))
    )
    (net (code "58") (name "Net-(U2-FB)") (class "Default")
      (node (ref "R5") (pin "1") (pinfunction "1_1") (pintype "passive"))
      (node (ref "U2") (pin "8") (pinfunction "FB_8") (pintype "bidirectional"))
    )
    (net (code "59") (name "Net-(U2-SS)") (class "Default")
      (node (ref "C7") (pin "2") (pinfunction "2_2") (pintype "passive"))
      (node (ref "U2") (pin "1") (pinfunction "SS_1") (pintype "bidirectional"))
    )
    (net (code "60") (name "Net-(U2-VCC)") (class "Default")
      (node (ref "C5") (pin "2") (pinfunction "2_2") (pintype "passive"))
      (node (ref "U2") (pin "7") (pinfunction "VCC_7") (pintype "bidirectional"))
    )
    (net (code "61") (name "Net-(U3-GPIO12)") (class "Default")
      (node (ref "R15") (pin "2") (pinfunction "2_2") (pintype "passive"))
      (node (ref "U3") (pin "6") (pinfunction "GPIO12_6") (pintype "bidirectional"))
    )
    (net (code "62") (name "Net-(U3-GPIO13)") (class "Default")
      (node (ref "R16") (pin "2") (pinfunction "2_2") (pintype "passive"))
      (node (ref "U3") (pin "7") (pinfunction "GPIO13_7") (pintype "bidirectional"))
    )
    (net (code "63") (name "Net-(U3-GPIO14)") (class "Default")
      (node (ref "R17") (pin "2") (pinfunction "2_2") (pintype "passive"))
      (node (ref "U3") (pin "5") (pinfunction "GPIO14_5") (pintype "bidirectional"))
    )
    (net (code "64") (name "Net-(U3-GPIO15)") (class "Default")
      (node (ref "R18") (pin "2") (pinfunction "2_2") (pintype "passive"))
      (node (ref "R20") (pin "2") (pinfunction "2_2") (pintype "passive"))
      (node (ref "U3") (pin "16") (pinfunction "GPIO15_16") (pintype "bidirectional"))
    )
    (net (code "65") (name "Net-(U3-GPIO16)") (class "Default")
      (node (ref "R19") (pin "2") (pinfunction "2_2") (pintype "passive"))
      (node (ref "U3") (pin "4") (pinfunction "GPIO16_4") (pintype "bidirectional"))
    )
    (net (code "66") (name "Net-(U3-RST)") (class "Default")
      (node (ref "R13") (pin "2") (pinfunction "2_2") (pintype "passive"))
      (node (ref "U3") (pin "1") (pinfunction "RST_1") (pintype "bidirectional"))
    )
    (net (code "67") (name "Net-(U3-RXD)") (class "Default")
      (node (ref "R22") (pin "1") (pinfunction "1_1") (pintype "passive"))
      (node (ref "U3") (pin "21") (pinfunction "RXD_21") (pintype "bidirectional"))
    )
    (net (code "68") (name "Net-(U3-TXD)") (class "Default")
      (node (ref "R21") (pin "1") (pinfunction "1_1") (pintype "passive"))
      (node (ref "U3") (pin "22") (pinfunction "TXD_22") (pintype "bidirectional"))
    )
    (net (code "69") (name "unconnected-(J2-Pad1)") (class "Default")
      (node (ref "J2") (pin "1") (pinfunction "1_1") (pintype "bidirectional"))
    )
    (net (code "70") (name "unconnected-(U3-ADC-Pad2)") (class "Default")
      (node (ref "U3") (pin "2") (pinfunction "ADC_2") (pintype "bidirectional"))
    )
    (net (code "71") (name "unconnected-(U3-CS0-Pad9)") (class "Default")
      (node (ref "U3") (pin "9") (pinfunction "CS0_9") (pintype "bidirectional"))
    )
    (net (code "72") (name "unconnected-(U3-IO9-Pad11)") (class "Default")
      (node (ref "U3") (pin "11") (pinfunction "IO9_11") (pintype "bidirectional"))
    )
    (net (code "73") (name "unconnected-(U3-IO10-Pad12)") (class "Default")
      (node (ref "U3") (pin "12") (pinfunction "IO10_12") (pintype "bidirectional"))
    )
    (net (code "74") (name "unconnected-(U3-MISO-Pad10)") (class "Default")
      (node (ref "U3") (pin "10") (pinfunction "MISO_10") (pintype "bidirectional"))
    )
    (net (code "75") (name "unconnected-(U3-MOSI-Pad13)") (class "Default")
      (node (ref "U3") (pin "13") (pinfunction "MOSI_13") (pintype "bidirectional"))
    )
    (net (code "76") (name "unconnected-(U3-SCLK-Pad14)") (class "Default")
      (node (ref "U3") (pin "14") (pinfunction "SCLK_14") (pintype "bidirectional"))
    )
    (net (code "77") (name "unconnected-(U4-NC1-Pad1)") (class "Default")
      (node (ref "U4") (pin "1") (pinfunction "NC1_1") (pintype "no_connect"))
    )
    (net (code "78") (name "unconnected-(U4-NC2-Pad2)") (class "Default")
      (node (ref "U4") (pin "2") (pinfunction "NC2_2") (pintype "no_connect"))
    )
    (net (code "79") (name "unconnected-(U4-NC3-Pad3)") (class "Default")
      (node (ref "U4") (pin "3") (pinfunction "NC3_3") (pintype "no_connect"))
    )
    (net (code "80") (name "unconnected-(U4-NC4-Pad7)") (class "Default")
      (node (ref "U4") (pin "7") (pinfunction "NC4_7") (pintype "no_connect"))
    )
    (net (code "81") (name "unconnected-(USB1-ID-Pad4)") (class "Default")
      (node (ref "USB1") (pin "4") (pinfunction "ID_4") (pintype "bidirectional"))
    )
  )
)
